# nguonsche.net
KiCad netlist of a schematic drawn in Altium Designer
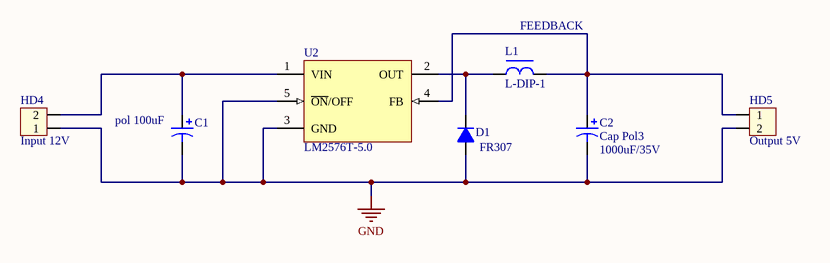
[diagram p0: nguonsche.SchDoc]

(export (version "E")
  (design (tool "Eeschema 10.0.6"))
  (components
    (comp (ref "C1")
      (value "pol 100uF")
      (footprint "C10mm")
      (description "Polarized Capacitor (Axial)")
      (fields (field (name "PUBLISHER") "Altium Limited"))
      (libsource (lib "My Library") (part "Cap Pol 12mm"))
    )
    (comp (ref "C2")
      (value "Cap Pol3")
      (footprint "CP2/5")
      (description "Polarized Capacitor (Surface Mount)")
      (fields (field (name "ALTIUM_VALUE") "1000uF/35V") (field (name "PUBLISHER") "Altium Limited"))
      (libsource (lib "syhaunguyen") (part "Cap Pol3"))
    )
    (comp (ref "D1")
      (value "FR307")
      (footprint "D2A")
      (description "Diode 1A")
      (libsource (lib "syhaunguyen") (part "D1A"))
    )
    (comp (ref "HD4")
      (value "Input 12V")
      (footprint "HED2")
      (description "Header 2 (Green)")
      (libsource (lib "") (part "Hed2_1"))
    )
    (comp (ref "HD5")
      (value "Output 5V")
      (footprint "HED2")
      (description "Header 2 (Green)")
      (libsource (lib "My Library") (part "Hed2"))
    )
    (comp (ref "L1")
      (value "L-DIP-1")
      (footprint "L-DIP-M-5.3")
      (description "Inductor")
      (libsource (lib "LIBRARY") (part "L-DIP-1"))
    )
    (comp (ref "U2")
      (value "LM2576T-5.0")
      (footprint "LM2576t")
      (description "SIMPLE SWITCHER; 3A Step-Down Voltage Regulator")
      (fields
        (field (name "MANUFACTURER") "National Semiconductor")
        (field (name "DIGIKEYPARTNUMBER") "LM2576T-5.0-ND")
        (field (name "PUBLISHER") "Altium Limited")
      )
      (libsource (lib "My Library") (part "LM2576T-5.0"))
    )
  )
  (nets
    (net (code "1") (name "GND") (class "Default")
      (node (ref "C1") (pin "2") (pinfunction "2_2") (pintype "passive"))
      (node (ref "C2") (pin "2") (pinfunction "2_2") (pintype "passive"))
      (node (ref "D1") (pin "1") (pinfunction "A_1") (pintype "passive"))
      (node (ref "HD4") (pin "1") (pinfunction "1_1") (pintype "passive"))
      (node (ref "HD5") (pin "2") (pinfunction "2_2") (pintype "passive"))
      (node (ref "U2") (pin "3") (pinfunction "GND_3") (pintype "power_in"))
      (node (ref "U2") (pin "5") (pinfunction "~{ON}/OFF_5") (pintype "input"))
    )
    (net (code "2") (name "Net-(D1-K)") (class "Default")
      (node (ref "D1") (pin "2") (pinfunction "K_2") (pintype "passive"))
      (node (ref "L1") (pin "1") (pinfunction "1_1") (pintype "passive"))
      (node (ref "U2") (pin "2") (pinfunction "OUT_2") (pintype "power_in"))
    )
    (net (code "3") (name "Net-(U2-FB)") (class "Default")
      (node (ref "C2") (pin "1") (pinfunction "1_1") (pintype "passive"))
      (node (ref "HD5") (pin "1") (pinfunction "1_1") (pintype "passive"))
      (node (ref "L1") (pin "2") (pinfunction "2_2") (pintype "passive"))
      (node (ref "U2") (pin "4") (pinfunction "FB_4") (pintype "input"))
    )
    (net (code "4") (name "Net-(U2-VIN)") (class "Default")
      (node (ref "C1") (pin "1") (pinfunction "1_1") (pintype "passive"))
      (node (ref "HD4") (pin "2") (pinfunction "2_2") (pintype "passive"))
      (node (ref "U2") (pin "1") (pinfunction "VIN_1") (pintype "power_in"))
    )
  )
)
